# djesaac.net
KiCad netlist of a schematic drawn in EAGLE
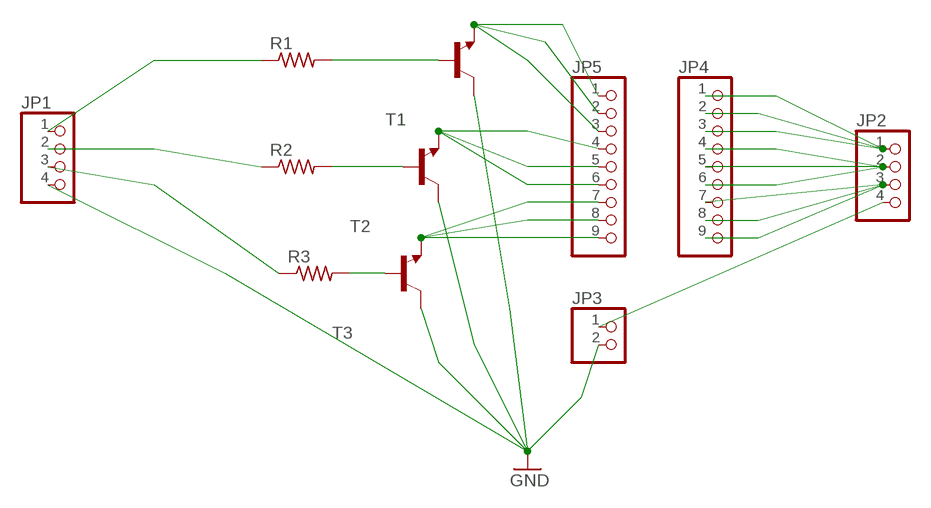
[diagram p0: schematic, sheet 1]

(export (version "E")
  (design (tool "Eeschema 10.0.6"))
  (components
    (comp (ref "JP1")
      (value "PINHD-1X4")
      (footprint "eagle-import:1X04")
      (libsource (lib "eagle-import") (part "PINHD-1X4"))
    )
    (comp (ref "JP2")
      (value "PINHD-1X4")
      (footprint "eagle-import:1X04")
      (libsource (lib "eagle-import") (part "PINHD-1X4"))
    )
    (comp (ref "JP3")
      (value "PINHD-1X2")
      (footprint "eagle-import:1X02")
      (libsource (lib "eagle-import") (part "PINHD-1X2"))
    )
    (comp (ref "JP4")
      (value "PINHD-1X9")
      (footprint "eagle-import:1X09")
      (libsource (lib "eagle-import") (part "PINHD-1X9"))
    )
    (comp (ref "JP5")
      (value "PINHD-1X9")
      (footprint "eagle-import:1X09")
      (libsource (lib "eagle-import") (part "PINHD-1X9"))
    )
    (comp (ref "R1")
      (value "R-US_0207/10")
      (footprint "eagle-import:0207_10")
      (libsource (lib "eagle-import") (part "R-US_0207/10"))
    )
    (comp (ref "R2")
      (value "R-US_0207/10")
      (footprint "eagle-import:0207_10")
      (libsource (lib "eagle-import") (part "R-US_0207/10"))
    )
    (comp (ref "R3")
      (value "R-US_0207/10")
      (footprint "eagle-import:0207_10")
      (libsource (lib "eagle-import") (part "R-US_0207/10"))
    )
    (comp (ref "T1")
      (value "-NPN-TO92-CBE")
      (footprint "eagle-import:TO92-CBE")
      (libsource (lib "eagle-import") (part "-NPN-TO92-CBE"))
    )
    (comp (ref "T2")
      (value "-NPN-TO92-CBE")
      (footprint "eagle-import:TO92-CBE")
      (libsource (lib "eagle-import") (part "-NPN-TO92-CBE"))
    )
    (comp (ref "T3")
      (value "-NPN-TO92-CBE")
      (footprint "eagle-import:TO92-CBE")
      (libsource (lib "eagle-import") (part "-NPN-TO92-CBE"))
    )
  )
  (nets
    (net (code "1") (name "GND") (class "Default")
      (node (ref "JP1") (pin "4") (pinfunction "4_4") (pintype "passive"))
      (node (ref "JP3") (pin "2") (pinfunction "2_2") (pintype "passive"))
      (node (ref "T1") (pin "C") (pinfunction "C_C") (pintype "passive"))
      (node (ref "T2") (pin "C") (pinfunction "C_C") (pintype "passive"))
      (node (ref "T3") (pin "C") (pinfunction "C_C") (pintype "passive"))
    )
    (net (code "2") (name "Net-(JP1-Pad1)") (class "Default")
      (node (ref "JP1") (pin "1") (pinfunction "1_1") (pintype "passive"))
      (node (ref "R1") (pin "1") (pinfunction "1_1") (pintype "passive"))
    )
    (net (code "3") (name "Net-(JP1-Pad2)") (class "Default")
      (node (ref "JP1") (pin "2") (pinfunction "2_2") (pintype "passive"))
      (node (ref "R2") (pin "1") (pinfunction "1_1") (pintype "passive"))
    )
    (net (code "4") (name "Net-(JP1-Pad3)") (class "Default")
      (node (ref "JP1") (pin "3") (pinfunction "3_3") (pintype "passive"))
      (node (ref "R3") (pin "1") (pinfunction "1_1") (pintype "passive"))
    )
    (net (code "5") (name "Net-(JP2-Pad1)") (class "Default")
      (node (ref "JP2") (pin "1") (pinfunction "1_1") (pintype "passive"))
      (node (ref "JP4") (pin "1") (pinfunction "1_1") (pintype "passive"))
      (node (ref "JP4") (pin "2") (pinfunction "2_2") (pintype "passive"))
      (node (ref "JP4") (pin "3") (pinfunction "3_3") (pintype "passive"))
    )
    (net (code "6") (name "Net-(JP2-Pad2)") (class "Default")
      (node (ref "JP2") (pin "2") (pinfunction "2_2") (pintype "passive"))
      (node (ref "JP4") (pin "4") (pinfunction "4_4") (pintype "passive"))
      (node (ref "JP4") (pin "5") (pinfunction "5_5") (pintype "passive"))
      (node (ref "JP4") (pin "6") (pinfunction "6_6") (pintype "passive"))
    )
    (net (code "7") (name "Net-(JP2-Pad3)") (class "Default")
      (node (ref "JP2") (pin "3") (pinfunction "3_3") (pintype "passive"))
      (node (ref "JP4") (pin "7") (pinfunction "7_7") (pintype "passive"))
      (node (ref "JP4") (pin "8") (pinfunction "8_8") (pintype "passive"))
      (node (ref "JP4") (pin "9") (pinfunction "9_9") (pintype "passive"))
    )
    (net (code "8") (name "Net-(JP2-Pad4)") (class "Default")
      (node (ref "JP2") (pin "4") (pinfunction "4_4") (pintype "passive"))
      (node (ref "JP3") (pin "1") (pinfunction "1_1") (pintype "passive"))
    )
    (net (code "9") (name "Net-(JP5-Pad1)") (class "Default")
      (node (ref "JP5") (pin "1") (pinfunction "1_1") (pintype "passive"))
      (node (ref "JP5") (pin "2") (pinfunction "2_2") (pintype "passive"))
      (node (ref "JP5") (pin "3") (pinfunction "3_3") (pintype "passive"))
      (node (ref "T1") (pin "E") (pinfunction "E_E") (pintype "passive"))
    )
    (net (code "10") (name "Net-(JP5-Pad4)") (class "Default")
      (node (ref "JP5") (pin "4") (pinfunction "4_4") (pintype "passive"))
      (node (ref "JP5") (pin "5") (pinfunction "5_5") (pintype "passive"))
      (node (ref "JP5") (pin "6") (pinfunction "6_6") (pintype "passive"))
      (node (ref "T2") (pin "E") (pinfunction "E_E") (pintype "passive"))
    )
    (net (code "11") (name "Net-(JP5-Pad7)") (class "Default")
      (node (ref "JP5") (pin "7") (pinfunction "7_7") (pintype "passive"))
      (node (ref "JP5") (pin "8") (pinfunction "8_8") (pintype "passive"))
      (node (ref "JP5") (pin "9") (pinfunction "9_9") (pintype "passive"))
      (node (ref "T3") (pin "E") (pinfunction "E_E") (pintype "passive"))
    )
    (net (code "12") (name "Net-(R1-Pad2)") (class "Default")
      (node (ref "R1") (pin "2") (pinfunction "2_2") (pintype "passive"))
      (node (ref "T1") (pin "B") (pinfunction "B_B") (pintype "passive"))
    )
    (net (code "13") (name "Net-(R2-Pad2)") (class "Default")
      (node (ref "R2") (pin "2") (pinfunction "2_2") (pintype "passive"))
      (node (ref "T2") (pin "B") (pinfunction "B_B") (pintype "passive"))
    )
    (net (code "14") (name "Net-(R3-Pad2)") (class "Default")
      (node (ref "R3") (pin "2") (pinfunction "2_2") (pintype "passive"))
      (node (ref "T3") (pin "B") (pinfunction "B_B") (pintype "passive"))
    )
  )
)
